# Sheet1.net
KiCad netlist of a schematic drawn in Altium Designer
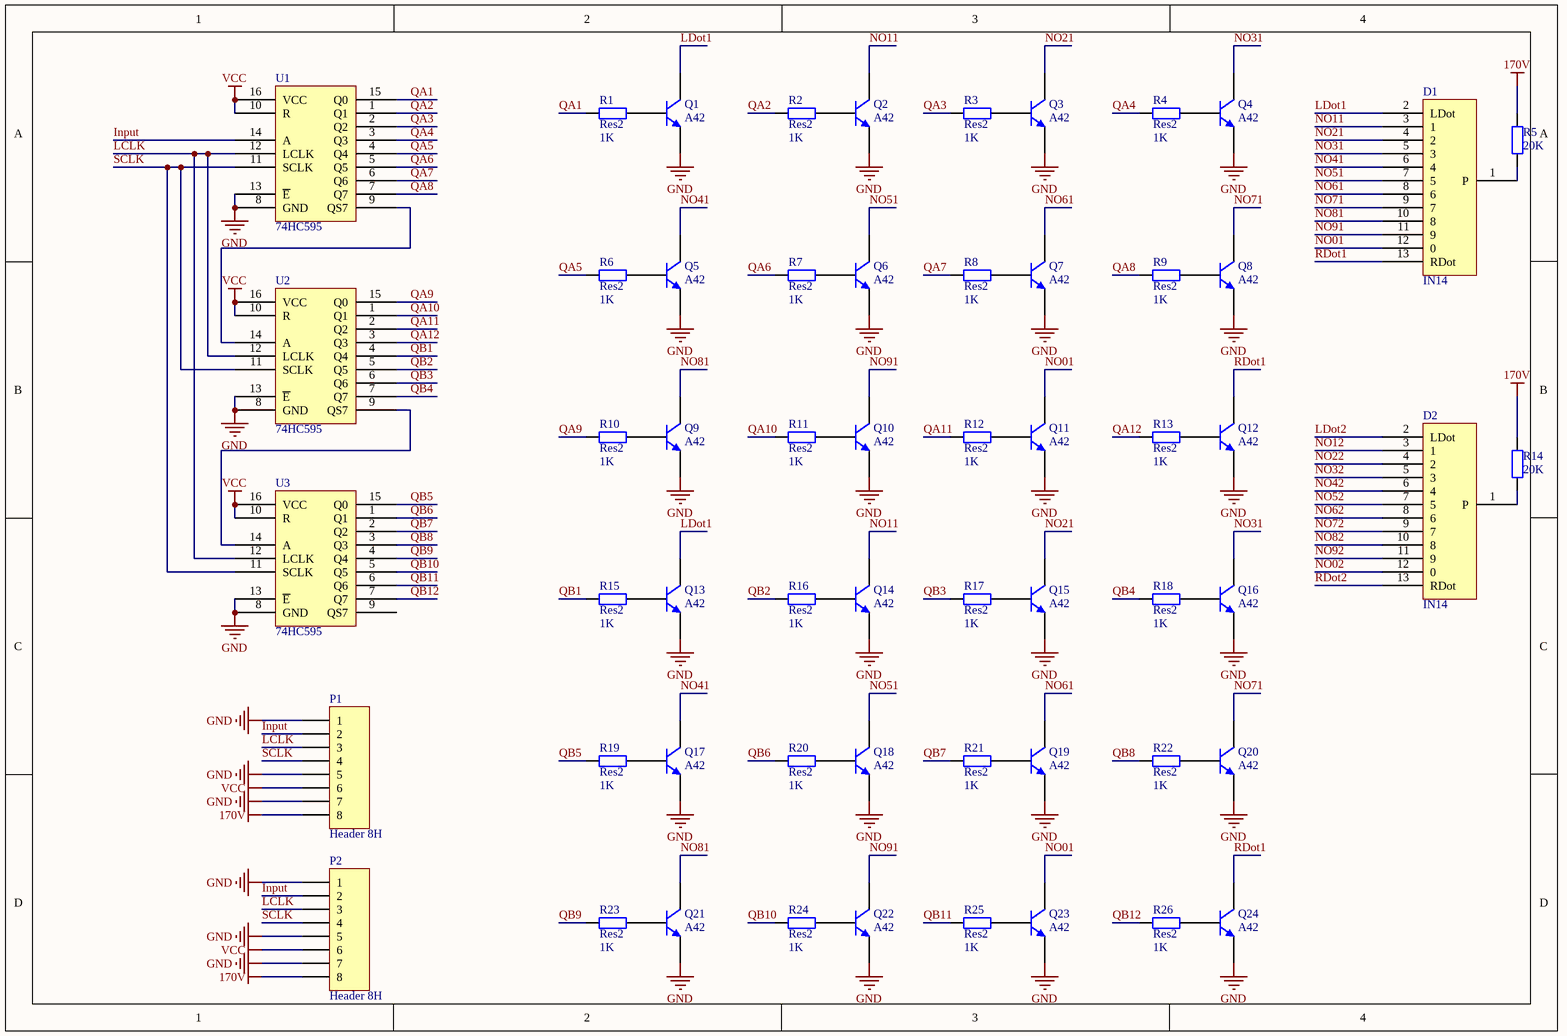
[diagram p0: Sheet1.SchDoc]

(export (version "E")
  (design (tool "Eeschema 10.0.6"))
  (components
    (comp (ref "D1") (value "IN14") (footprint "IN14") (libsource (lib "Schlib1") (part "IN14")))
    (comp (ref "D2") (value "IN14") (footprint "IN14") (libsource (lib "Schlib1") (part "IN14")))
    (comp (ref "P1")
      (value "Header 8H")
      (footprint "HDR1X8H")
      (description "Header, 8-Pin, Right Angle")
      (fields (field (name "PUBLISHER") "Altium Limited"))
      (libsource (lib "Miscellaneous Connectors") (part "Header 8H"))
    )
    (comp (ref "P2")
      (value "Header 8H")
      (footprint "HDR1X8H")
      (description "Header, 8-Pin, Right Angle")
      (fields (field (name "PUBLISHER") "Altium Limited"))
      (libsource (lib "Miscellaneous Connectors") (part "Header 8H"))
    )
    (comp (ref "Q1")
      (value "A42")
      (footprint "SOT-23")
      (description "NPN General Purpose Amplifier")
      (fields (field (name "PUBLISHER") "Altium Limited"))
      (libsource (lib "Miscellaneous Devices") (part "2N3904"))
    )
    (comp (ref "Q2")
      (value "A42")
      (footprint "SOT-23")
      (description "NPN General Purpose Amplifier")
      (fields (field (name "PUBLISHER") "Altium Limited"))
      (libsource (lib "Miscellaneous Devices") (part "2N3904"))
    )
    (comp (ref "Q3")
      (value "A42")
      (footprint "SOT-23")
      (description "NPN General Purpose Amplifier")
      (fields (field (name "PUBLISHER") "Altium Limited"))
      (libsource (lib "Miscellaneous Devices") (part "2N3904"))
    )
    (comp (ref "Q4")
      (value "A42")
      (footprint "SOT-23")
      (description "NPN General Purpose Amplifier")
      (fields (field (name "PUBLISHER") "Altium Limited"))
      (libsource (lib "Miscellaneous Devices") (part "2N3904"))
    )
    (comp (ref "Q5")
      (value "A42")
      (footprint "SOT-23")
      (description "NPN General Purpose Amplifier")
      (fields (field (name "PUBLISHER") "Altium Limited"))
      (libsource (lib "Miscellaneous Devices") (part "2N3904"))
    )
    (comp (ref "Q6")
      (value "A42")
      (footprint "SOT-23")
      (description "NPN General Purpose Amplifier")
      (fields (field (name "PUBLISHER") "Altium Limited"))
      (libsource (lib "Miscellaneous Devices") (part "2N3904"))
    )
    (comp (ref "Q7")
      (value "A42")
      (footprint "SOT-23")
      (description "NPN General Purpose Amplifier")
      (fields (field (name "PUBLISHER") "Altium Limited"))
      (libsource (lib "Miscellaneous Devices") (part "2N3904"))
    )
    (comp (ref "Q8")
      (value "A42")
      (footprint "SOT-23")
      (description "NPN General Purpose Amplifier")
      (fields (field (name "PUBLISHER") "Altium Limited"))
      (libsource (lib "Miscellaneous Devices") (part "2N3904"))
    )
    (comp (ref "Q9")
      (value "A42")
      (footprint "SOT-23")
      (description "NPN General Purpose Amplifier")
      (fields (field (name "PUBLISHER") "Altium Limited"))
      (libsource (lib "Miscellaneous Devices") (part "2N3904"))
    )
    (comp (ref "Q10")
      (value "A42")
      (footprint "SOT-23")
      (description "NPN General Purpose Amplifier")
      (fields (field (name "PUBLISHER") "Altium Limited"))
      (libsource (lib "Miscellaneous Devices") (part "2N3904"))
    )
    (comp (ref "Q11")
      (value "A42")
      (footprint "SOT-23")
      (description "NPN General Purpose Amplifier")
      (fields (field (name "PUBLISHER") "Altium Limited"))
      (libsource (lib "Miscellaneous Devices") (part "2N3904"))
    )
    (comp (ref "Q12")
      (value "A42")
      (footprint "SOT-23")
      (description "NPN General Purpose Amplifier")
      (fields (field (name "PUBLISHER") "Altium Limited"))
      (libsource (lib "Miscellaneous Devices") (part "2N3904"))
    )
    (comp (ref "Q13")
      (value "A42")
      (footprint "SOT-23")
      (description "NPN General Purpose Amplifier")
      (fields (field (name "PUBLISHER") "Altium Limited"))
      (libsource (lib "Miscellaneous Devices") (part "2N3904"))
    )
    (comp (ref "Q14")
      (value "A42")
      (footprint "SOT-23")
      (description "NPN General Purpose Amplifier")
      (fields (field (name "PUBLISHER") "Altium Limited"))
      (libsource (lib "Miscellaneous Devices") (part "2N3904"))
    )
    (comp (ref "Q15")
      (value "A42")
      (footprint "SOT-23")
      (description "NPN General Purpose Amplifier")
      (fields (field (name "PUBLISHER") "Altium Limited"))
      (libsource (lib "Miscellaneous Devices") (part "2N3904"))
    )
    (comp (ref "Q16")
      (value "A42")
      (footprint "SOT-23")
      (description "NPN General Purpose Amplifier")
      (fields (field (name "PUBLISHER") "Altium Limited"))
      (libsource (lib "Miscellaneous Devices") (part "2N3904"))
    )
    (comp (ref "Q17")
      (value "A42")
      (footprint "SOT-23")
      (description "NPN General Purpose Amplifier")
      (fields (field (name "PUBLISHER") "Altium Limited"))
      (libsource (lib "Miscellaneous Devices") (part "2N3904"))
    )
    (comp (ref "Q18")
      (value "A42")
      (footprint "SOT-23")
      (description "NPN General Purpose Amplifier")
      (fields (field (name "PUBLISHER") "Altium Limited"))
      (libsource (lib "Miscellaneous Devices") (part "2N3904"))
    )
    (comp (ref "Q19")
      (value "A42")
      (footprint "SOT-23")
      (description "NPN General Purpose Amplifier")
      (fields (field (name "PUBLISHER") "Altium Limited"))
      (libsource (lib "Miscellaneous Devices") (part "2N3904"))
    )
    (comp (ref "Q20")
      (value "A42")
      (footprint "SOT-23")
      (description "NPN General Purpose Amplifier")
      (fields (field (name "PUBLISHER") "Altium Limited"))
      (libsource (lib "Miscellaneous Devices") (part "2N3904"))
    )
    (comp (ref "Q21")
      (value "A42")
      (footprint "SOT-23")
      (description "NPN General Purpose Amplifier")
      (fields (field (name "PUBLISHER") "Altium Limited"))
      (libsource (lib "Miscellaneous Devices") (part "2N3904"))
    )
    (comp (ref "Q22")
      (value "A42")
      (footprint "SOT-23")
      (description "NPN General Purpose Amplifier")
      (fields (field (name "PUBLISHER") "Altium Limited"))
      (libsource (lib "Miscellaneous Devices") (part "2N3904"))
    )
    (comp (ref "Q23")
      (value "A42")
      (footprint "SOT-23")
      (description "NPN General Purpose Amplifier")
      (fields (field (name "PUBLISHER") "Altium Limited"))
      (libsource (lib "Miscellaneous Devices") (part "2N3904"))
    )
    (comp (ref "Q24")
      (value "A42")
      (footprint "SOT-23")
      (description "NPN General Purpose Amplifier")
      (fields (field (name "PUBLISHER") "Altium Limited"))
      (libsource (lib "Miscellaneous Devices") (part "2N3904"))
    )
    (comp (ref "R1")
      (value "Res2")
      (footprint "0805-0R")
      (description "Resistor")
      (fields (field (name "ALTIUM_VALUE") "1K") (field (name "PUBLISHER") "Altium Limited"))
      (libsource (lib "Miscellaneous Devices") (part "Res2"))
    )
    (comp (ref "R2")
      (value "Res2")
      (footprint "AXIAL-0.4")
      (description "Resistor")
      (fields (field (name "ALTIUM_VALUE") "1K") (field (name "PUBLISHER") "Altium Limited"))
      (libsource (lib "Miscellaneous Devices") (part "Res2"))
    )
    (comp (ref "R3")
      (value "Res2")
      (footprint "AXIAL-0.4")
      (description "Resistor")
      (fields (field (name "ALTIUM_VALUE") "1K") (field (name "PUBLISHER") "Altium Limited"))
      (libsource (lib "Miscellaneous Devices") (part "Res2"))
    )
    (comp (ref "R4")
      (value "Res2")
      (footprint "AXIAL-0.4")
      (description "Resistor")
      (fields (field (name "ALTIUM_VALUE") "1K") (field (name "PUBLISHER") "Altium Limited"))
      (libsource (lib "Miscellaneous Devices") (part "Res2"))
    )
    (comp (ref "R5")
      (value "20K")
      (footprint "0805-0R")
      (description "Resistor")
      (fields (field (name "PUBLISHER") "Altium Limited"))
      (libsource (lib "") (part "Res2_1"))
    )
    (comp (ref "R6")
      (value "Res2")
      (footprint "AXIAL-0.4")
      (description "Resistor")
      (fields (field (name "ALTIUM_VALUE") "1K") (field (name "PUBLISHER") "Altium Limited"))
      (libsource (lib "Miscellaneous Devices") (part "Res2"))
    )
    (comp (ref "R7")
      (value "Res2")
      (footprint "AXIAL-0.4")
      (description "Resistor")
      (fields (field (name "ALTIUM_VALUE") "1K") (field (name "PUBLISHER") "Altium Limited"))
      (libsource (lib "Miscellaneous Devices") (part "Res2"))
    )
    (comp (ref "R8")
      (value "Res2")
      (footprint "AXIAL-0.4")
      (description "Resistor")
      (fields (field (name "ALTIUM_VALUE") "1K") (field (name "PUBLISHER") "Altium Limited"))
      (libsource (lib "Miscellaneous Devices") (part "Res2"))
    )
    (comp (ref "R9")
      (value "Res2")
      (footprint "AXIAL-0.4")
      (description "Resistor")
      (fields (field (name "ALTIUM_VALUE") "1K") (field (name "PUBLISHER") "Altium Limited"))
      (libsource (lib "Miscellaneous Devices") (part "Res2"))
    )
    (comp (ref "R10")
      (value "Res2")
      (footprint "AXIAL-0.4")
      (description "Resistor")
      (fields (field (name "ALTIUM_VALUE") "1K") (field (name "PUBLISHER") "Altium Limited"))
      (libsource (lib "Miscellaneous Devices") (part "Res2"))
    )
    (comp (ref "R11")
      (value "Res2")
      (footprint "AXIAL-0.4")
      (description "Resistor")
      (fields (field (name "ALTIUM_VALUE") "1K") (field (name "PUBLISHER") "Altium Limited"))
      (libsource (lib "Miscellaneous Devices") (part "Res2"))
    )
    (comp (ref "R12")
      (value "Res2")
      (footprint "AXIAL-0.4")
      (description "Resistor")
      (fields (field (name "ALTIUM_VALUE") "1K") (field (name "PUBLISHER") "Altium Limited"))
      (libsource (lib "Miscellaneous Devices") (part "Res2"))
    )
    (comp (ref "R13")
      (value "Res2")
      (footprint "AXIAL-0.4")
      (description "Resistor")
      (fields (field (name "ALTIUM_VALUE") "1K") (field (name "PUBLISHER") "Altium Limited"))
      (libsource (lib "Miscellaneous Devices") (part "Res2"))
    )
    (comp (ref "R14")
      (value "20K")
      (footprint "0805-0R")
      (description "Resistor")
      (fields (field (name "PUBLISHER") "Altium Limited"))
      (libsource (lib "") (part "Res2_1"))
    )
    (comp (ref "R15")
      (value "Res2")
      (footprint "AXIAL-0.4")
      (description "Resistor")
      (fields (field (name "ALTIUM_VALUE") "1K") (field (name "PUBLISHER") "Altium Limited"))
      (libsource (lib "Miscellaneous Devices") (part "Res2"))
    )
    (comp (ref "R16")
      (value "Res2")
      (footprint "AXIAL-0.4")
      (description "Resistor")
      (fields (field (name "ALTIUM_VALUE") "1K") (field (name "PUBLISHER") "Altium Limited"))
      (libsource (lib "Miscellaneous Devices") (part "Res2"))
    )
    (comp (ref "R17")
      (value "Res2")
      (footprint "AXIAL-0.4")
      (description "Resistor")
      (fields (field (name "ALTIUM_VALUE") "1K") (field (name "PUBLISHER") "Altium Limited"))
      (libsource (lib "Miscellaneous Devices") (part "Res2"))
    )
    (comp (ref "R18")
      (value "Res2")
      (footprint "AXIAL-0.4")
      (description "Resistor")
      (fields (field (name "ALTIUM_VALUE") "1K") (field (name "PUBLISHER") "Altium Limited"))
      (libsource (lib "Miscellaneous Devices") (part "Res2"))
    )
    (comp (ref "R19")
      (value "Res2")
      (footprint "AXIAL-0.4")
      (description "Resistor")
      (fields (field (name "ALTIUM_VALUE") "1K") (field (name "PUBLISHER") "Altium Limited"))
      (libsource (lib "Miscellaneous Devices") (part "Res2"))
    )
    (comp (ref "R20")
      (value "Res2")
      (footprint "AXIAL-0.4")
      (description "Resistor")
      (fields (field (name "ALTIUM_VALUE") "1K") (field (name "PUBLISHER") "Altium Limited"))
      (libsource (lib "Miscellaneous Devices") (part "Res2"))
    )
    (comp (ref "R21")
      (value "Res2")
      (footprint "AXIAL-0.4")
      (description "Resistor")
      (fields (field (name "ALTIUM_VALUE") "1K") (field (name "PUBLISHER") "Altium Limited"))
      (libsource (lib "Miscellaneous Devices") (part "Res2"))
    )
    (comp (ref "R22")
      (value "Res2")
      (footprint "AXIAL-0.4")
      (description "Resistor")
      (fields (field (name "ALTIUM_VALUE") "1K") (field (name "PUBLISHER") "Altium Limited"))
      (libsource (lib "Miscellaneous Devices") (part "Res2"))
    )
    (comp (ref "R23")
      (value "Res2")
      (footprint "AXIAL-0.4")
      (description "Resistor")
      (fields (field (name "ALTIUM_VALUE") "1K") (field (name "PUBLISHER") "Altium Limited"))
      (libsource (lib "Miscellaneous Devices") (part "Res2"))
    )
    (comp (ref "R24")
      (value "Res2")
      (footprint "AXIAL-0.4")
      (description "Resistor")
      (fields (field (name "ALTIUM_VALUE") "1K") (field (name "PUBLISHER") "Altium Limited"))
      (libsource (lib "Miscellaneous Devices") (part "Res2"))
    )
    (comp (ref "R25")
      (value "Res2")
      (footprint "AXIAL-0.4")
      (description "Resistor")
      (fields (field (name "ALTIUM_VALUE") "1K") (field (name "PUBLISHER") "Altium Limited"))
      (libsource (lib "Miscellaneous Devices") (part "Res2"))
    )
    (comp (ref "R26")
      (value "Res2")
      (footprint "AXIAL-0.4")
      (description "Resistor")
      (fields (field (name "ALTIUM_VALUE") "1K") (field (name "PUBLISHER") "Altium Limited"))
      (libsource (lib "Miscellaneous Devices") (part "Res2"))
    )
    (comp (ref "U1") (value "74HC595") (footprint "SOP16") (libsource (lib "74HC595") (part "74HC595")))
    (comp (ref "U2") (value "74HC595") (footprint "SOP16") (libsource (lib "74HC595") (part "74HC595")))
    (comp (ref "U3") (value "74HC595") (footprint "SOP16") (libsource (lib "74HC595") (part "74HC595")))
  )
  (nets
    (net (code "1") (name "/Input") (class "Default")
      (node (ref "P1") (pin "2") (pinfunction "2_2") (pintype "passive"))
      (node (ref "P2") (pin "2") (pinfunction "2_2") (pintype "passive"))
      (node (ref "U1") (pin "14") (pinfunction "A_14") (pintype "passive"))
    )
    (net (code "2") (name "/LCLK") (class "Default")
      (node (ref "P1") (pin "3") (pinfunction "3_3") (pintype "passive"))
      (node (ref "P2") (pin "3") (pinfunction "3_3") (pintype "passive"))
      (node (ref "U1") (pin "12") (pinfunction "LCLK_12") (pintype "passive"))
      (node (ref "U2") (pin "12") (pinfunction "LCLK_12") (pintype "passive"))
      (node (ref "U3") (pin "12") (pinfunction "LCLK_12") (pintype "passive"))
    )
    (net (code "3") (name "/LDot1") (class "Default")
      (node (ref "D1") (pin "2") (pinfunction "LDot_2") (pintype "passive"))
      (node (ref "Q1") (pin "3") (pinfunction "C_3") (pintype "passive"))
      (node (ref "Q13") (pin "3") (pinfunction "C_3") (pintype "passive"))
    )
    (net (code "4") (name "/LDot2") (class "Default")
      (node (ref "D2") (pin "2") (pinfunction "LDot_2") (pintype "passive"))
    )
    (net (code "5") (name "/NO01") (class "Default")
      (node (ref "D1") (pin "12") (pinfunction "0_12") (pintype "passive"))
      (node (ref "Q11") (pin "3") (pinfunction "C_3") (pintype "passive"))
      (node (ref "Q23") (pin "3") (pinfunction "C_3") (pintype "passive"))
    )
    (net (code "6") (name "/NO02") (class "Default")
      (node (ref "D2") (pin "12") (pinfunction "0_12") (pintype "passive"))
    )
    (net (code "7") (name "/NO11") (class "Default")
      (node (ref "D1") (pin "3") (pinfunction "1_3") (pintype "passive"))
      (node (ref "Q14") (pin "3") (pinfunction "C_3") (pintype "passive"))
      (node (ref "Q2") (pin "3") (pinfunction "C_3") (pintype "passive"))
    )
    (net (code "8") (name "/NO12") (class "Default")
      (node (ref "D2") (pin "3") (pinfunction "1_3") (pintype "passive"))
    )
    (net (code "9") (name "/NO21") (class "Default")
      (node (ref "D1") (pin "4") (pinfunction "2_4") (pintype "passive"))
      (node (ref "Q15") (pin "3") (pinfunction "C_3") (pintype "passive"))
      (node (ref "Q3") (pin "3") (pinfunction "C_3") (pintype "passive"))
    )
    (net (code "10") (name "/NO22") (class "Default")
      (node (ref "D2") (pin "4") (pinfunction "2_4") (pintype "passive"))
    )
    (net (code "11") (name "/NO31") (class "Default")
      (node (ref "D1") (pin "5") (pinfunction "3_5") (pintype "passive"))
      (node (ref "Q16") (pin "3") (pinfunction "C_3") (pintype "passive"))
      (node (ref "Q4") (pin "3") (pinfunction "C_3") (pintype "passive"))
    )
    (net (code "12") (name "/NO32") (class "Default")
      (node (ref "D2") (pin "5") (pinfunction "3_5") (pintype "passive"))
    )
    (net (code "13") (name "/NO41") (class "Default")
      (node (ref "D1") (pin "6") (pinfunction "4_6") (pintype "passive"))
      (node (ref "Q17") (pin "3") (pinfunction "C_3") (pintype "passive"))
      (node (ref "Q5") (pin "3") (pinfunction "C_3") (pintype "passive"))
    )
    (net (code "14") (name "/NO42") (class "Default")
      (node (ref "D2") (pin "6") (pinfunction "4_6") (pintype "passive"))
    )
    (net (code "15") (name "/NO51") (class "Default")
      (node (ref "D1") (pin "7") (pinfunction "5_7") (pintype "passive"))
      (node (ref "Q18") (pin "3") (pinfunction "C_3") (pintype "passive"))
      (node (ref "Q6") (pin "3") (pinfunction "C_3") (pintype "passive"))
    )
    (net (code "16") (name "/NO52") (class "Default")
      (node (ref "D2") (pin "7") (pinfunction "5_7") (pintype "passive"))
    )
    (net (code "17") (name "/NO61") (class "Default")
      (node (ref "D1") (pin "8") (pinfunction "6_8") (pintype "passive"))
      (node (ref "Q19") (pin "3") (pinfunction "C_3") (pintype "passive"))
      (node (ref "Q7") (pin "3") (pinfunction "C_3") (pintype "passive"))
    )
    (net (code "18") (name "/NO62") (class "Default")
      (node (ref "D2") (pin "8") (pinfunction "6_8") (pintype "passive"))
    )
    (net (code "19") (name "/NO71") (class "Default")
      (node (ref "D1") (pin "9") (pinfunction "7_9") (pintype "passive"))
      (node (ref "Q20") (pin "3") (pinfunction "C_3") (pintype "passive"))
      (node (ref "Q8") (pin "3") (pinfunction "C_3") (pintype "passive"))
    )
    (net (code "20") (name "/NO72") (class "Default")
      (node (ref "D2") (pin "9") (pinfunction "7_9") (pintype "passive"))
    )
    (net (code "21") (name "/NO81") (class "Default")
      (node (ref "D1") (pin "10") (pinfunction "8_10") (pintype "passive"))
      (node (ref "Q21") (pin "3") (pinfunction "C_3") (pintype "passive"))
      (node (ref "Q9") (pin "3") (pinfunction "C_3") (pintype "passive"))
    )
    (net (code "22") (name "/NO82") (class "Default")
      (node (ref "D2") (pin "10") (pinfunction "8_10") (pintype "passive"))
    )
    (net (code "23") (name "/NO91") (class "Default")
      (node (ref "D1") (pin "11") (pinfunction "9_11") (pintype "passive"))
      (node (ref "Q10") (pin "3") (pinfunction "C_3") (pintype "passive"))
      (node (ref "Q22") (pin "3") (pinfunction "C_3") (pintype "passive"))
    )
    (net (code "24") (name "/NO92") (class "Default")
      (node (ref "D2") (pin "11") (pinfunction "9_11") (pintype "passive"))
    )
    (net (code "25") (name "/QA1") (class "Default")
      (node (ref "R1") (pin "1") (pinfunction "1_1") (pintype "passive"))
      (node (ref "U1") (pin "15") (pinfunction "Q0_15") (pintype "passive"))
    )
    (net (code "26") (name "/QA2") (class "Default")
      (node (ref "R2") (pin "1") (pinfunction "1_1") (pintype "passive"))
      (node (ref "U1") (pin "1") (pinfunction "Q1_1") (pintype "passive"))
    )
    (net (code "27") (name "/QA3") (class "Default")
      (node (ref "R3") (pin "1") (pinfunction "1_1") (pintype "passive"))
      (node (ref "U1") (pin "2") (pinfunction "Q2_2") (pintype "passive"))
    )
    (net (code "28") (name "/QA4") (class "Default")
      (node (ref "R4") (pin "1") (pinfunction "1_1") (pintype "passive"))
      (node (ref "U1") (pin "3") (pinfunction "Q3_3") (pintype "passive"))
    )
    (net (code "29") (name "/QA5") (class "Default")
      (node (ref "R6") (pin "1") (pinfunction "1_1") (pintype "passive"))
      (node (ref "U1") (pin "4") (pinfunction "Q4_4") (pintype "passive"))
    )
    (net (code "30") (name "/QA6") (class "Default")
      (node (ref "R7") (pin "1") (pinfunction "1_1") (pintype "passive"))
      (node (ref "U1") (pin "5") (pinfunction "Q5_5") (pintype "passive"))
    )
    (net (code "31") (name "/QA7") (class "Default")
      (node (ref "R8") (pin "1") (pinfunction "1_1") (pintype "passive"))
      (node (ref "U1") (pin "6") (pinfunction "Q6_6") (pintype "passive"))
    )
    (net (code "32") (name "/QA8") (class "Default")
      (node (ref "R9") (pin "1") (pinfunction "1_1") (pintype "passive"))
      (node (ref "U1") (pin "7") (pinfunction "Q7_7") (pintype "passive"))
    )
    (net (code "33") (name "/QA9") (class "Default")
      (node (ref "R10") (pin "1") (pinfunction "1_1") (pintype "passive"))
      (node (ref "U2") (pin "15") (pinfunction "Q0_15") (pintype "passive"))
    )
    (net (code "34") (name "/QA10") (class "Default")
      (node (ref "R11") (pin "1") (pinfunction "1_1") (pintype "passive"))
      (node (ref "U2") (pin "1") (pinfunction "Q1_1") (pintype "passive"))
    )
    (net (code "35") (name "/QA11") (class "Default")
      (node (ref "R12") (pin "1") (pinfunction "1_1") (pintype "passive"))
      (node (ref "U2") (pin "2") (pinfunction "Q2_2") (pintype "passive"))
    )
    (net (code "36") (name "/QA12") (class "Default")
      (node (ref "R13") (pin "1") (pinfunction "1_1") (pintype "passive"))
      (node (ref "U2") (pin "3") (pinfunction "Q3_3") (pintype "passive"))
    )
    (net (code "37") (name "/QB1") (class "Default")
      (node (ref "R15") (pin "1") (pinfunction "1_1") (pintype "passive"))
      (node (ref "U2") (pin "4") (pinfunction "Q4_4") (pintype "passive"))
    )
    (net (code "38") (name "/QB2") (class "Default")
      (node (ref "R16") (pin "1") (pinfunction "1_1") (pintype "passive"))
      (node (ref "U2") (pin "5") (pinfunction "Q5_5") (pintype "passive"))
    )
    (net (code "39") (name "/QB3") (class "Default")
      (node (ref "R17") (pin "1") (pinfunction "1_1") (pintype "passive"))
      (node (ref "U2") (pin "6") (pinfunction "Q6_6") (pintype "passive"))
    )
    (net (code "40") (name "/QB4") (class "Default")
      (node (ref "R18") (pin "1") (pinfunction "1_1") (pintype "passive"))
      (node (ref "U2") (pin "7") (pinfunction "Q7_7") (pintype "passive"))
    )
    (net (code "41") (name "/QB5") (class "Default")
      (node (ref "R19") (pin "1") (pinfunction "1_1") (pintype "passive"))
      (node (ref "U3") (pin "15") (pinfunction "Q0_15") (pintype "passive"))
    )
    (net (code "42") (name "/QB6") (class "Default")
      (node (ref "R20") (pin "1") (pinfunction "1_1") (pintype "passive"))
      (node (ref "U3") (pin "1") (pinfunction "Q1_1") (pintype "passive"))
    )
    (net (code "43") (name "/QB7") (class "Default")
      (node (ref "R21") (pin "1") (pinfunction "1_1") (pintype "passive"))
      (node (ref "U3") (pin "2") (pinfunction "Q2_2") (pintype "passive"))
    )
    (net (code "44") (name "/QB8") (class "Default")
      (node (ref "R22") (pin "1") (pinfunction "1_1") (pintype "passive"))
      (node (ref "U3") (pin "3") (pinfunction "Q3_3") (pintype "passive"))
    )
    (net (code "45") (name "/QB9") (class "Default")
      (node (ref "R23") (pin "1") (pinfunction "1_1") (pintype "passive"))
      (node (ref "U3") (pin "4") (pinfunction "Q4_4") (pintype "passive"))
    )
    (net (code "46") (name "/QB10") (class "Default")
      (node (ref "R24") (pin "1") (pinfunction "1_1") (pintype "passive"))
      (node (ref "U3") (pin "5") (pinfunction "Q5_5") (pintype "passive"))
    )
    (net (code "47") (name "/QB11") (class "Default")
      (node (ref "R25") (pin "1") (pinfunction "1_1") (pintype "passive"))
      (node (ref "U3") (pin "6") (pinfunction "Q6_6") (pintype "passive"))
    )
    (net (code "48") (name "/QB12") (class "Default")
      (node (ref "R26") (pin "1") (pinfunction "1_1") (pintype "passive"))
      (node (ref "U3") (pin "7") (pinfunction "Q7_7") (pintype "passive"))
    )
    (net (code "49") (name "/RDot1") (class "Default")
      (node (ref "D1") (pin "13") (pinfunction "RDot_13") (pintype "passive"))
      (node (ref "Q12") (pin "3") (pinfunction "C_3") (pintype "passive"))
      (node (ref "Q24") (pin "3") (pinfunction "C_3") (pintype "passive"))
    )
    (net (code "50") (name "/RDot2") (class "Default")
      (node (ref "D2") (pin "13") (pinfunction "RDot_13") (pintype "passive"))
    )
    (net (code "51") (name "/SCLK") (class "Default")
      (node (ref "P1") (pin "4") (pinfunction "4_4") (pintype "passive"))
      (node (ref "P2") (pin "4") (pinfunction "4_4") (pintype "passive"))
      (node (ref "U1") (pin "11") (pinfunction "SCLK_11") (pintype "passive"))
      (node (ref "U2") (pin "11") (pinfunction "SCLK_11") (pintype "passive"))
      (node (ref "U3") (pin "11") (pinfunction "SCLK_11") (pintype "passive"))
    )
    (net (code "52") (name "170V") (class "Default")
      (node (ref "P1") (pin "8") (pinfunction "8_8") (pintype "passive"))
      (node (ref "P2") (pin "8") (pinfunction "8_8") (pintype "passive"))
      (node (ref "R14") (pin "2") (pinfunction "2_2") (pintype "passive"))
      (node (ref "R5") (pin "2") (pinfunction "2_2") (pintype "passive"))
    )
    (net (code "53") (name "GND") (class "Default")
      (node (ref "P1") (pin "1") (pinfunction "1_1") (pintype "passive"))
      (node (ref "P1") (pin "5") (pinfunction "5_5") (pintype "passive"))
      (node (ref "P1") (pin "7") (pinfunction "7_7") (pintype "passive"))
      (node (ref "P2") (pin "1") (pinfunction "1_1") (pintype "passive"))
      (node (ref "P2") (pin "5") (pinfunction "5_5") (pintype "passive"))
      (node (ref "P2") (pin "7") (pinfunction "7_7") (pintype "passive"))
      (node (ref "Q1") (pin "1") (pinfunction "E_1") (pintype "passive"))
      (node (ref "Q10") (pin "1") (pinfunction "E_1") (pintype "passive"))
      (node (ref "Q11") (pin "1") (pinfunction "E_1") (pintype "passive"))
      (node (ref "Q12") (pin "1") (pinfunction "E_1") (pintype "passive"))
      (node (ref "Q13") (pin "1") (pinfunction "E_1") (pintype "passive"))
      (node (ref "Q14") (pin "1") (pinfunction "E_1") (pintype "passive"))
      (node (ref "Q15") (pin "1") (pinfunction "E_1") (pintype "passive"))
      (node (ref "Q16") (pin "1") (pinfunction "E_1") (pintype "passive"))
      (node (ref "Q17") (pin "1") (pinfunction "E_1") (pintype "passive"))
      (node (ref "Q18") (pin "1") (pinfunction "E_1") (pintype "passive"))
      (node (ref "Q19") (pin "1") (pinfunction "E_1") (pintype "passive"))
      (node (ref "Q2") (pin "1") (pinfunction "E_1") (pintype "passive"))
      (node (ref "Q20") (pin "1") (pinfunction "E_1") (pintype "passive"))
      (node (ref "Q21") (pin "1") (pinfunction "E_1") (pintype "passive"))
      (node (ref "Q22") (pin "1") (pinfunction "E_1") (pintype "passive"))
      (node (ref "Q23") (pin "1") (pinfunction "E_1") (pintype "passive"))
      (node (ref "Q24") (pin "1") (pinfunction "E_1") (pintype "passive"))
      (node (ref "Q3") (pin "1") (pinfunction "E_1") (pintype "passive"))
      (node (ref "Q4") (pin "1") (pinfunction "E_1") (pintype "passive"))
      (node (ref "Q5") (pin "1") (pinfunction "E_1") (pintype "passive"))
      (node (ref "Q6") (pin "1") (pinfunction "E_1") (pintype "passive"))
      (node (ref "Q7") (pin "1") (pinfunction "E_1") (pintype "passive"))
      (node (ref "Q8") (pin "1") (pinfunction "E_1") (pintype "passive"))
      (node (ref "Q9") (pin "1") (pinfunction "E_1") (pintype "passive"))
      (node (ref "U1") (pin "13") (pinfunction "~{E}_13") (pintype "passive"))
      (node (ref "U1") (pin "8") (pinfunction "GND_8") (pintype "passive"))
      (node (ref "U2") (pin "13") (pinfunction "~{E}_13") (pintype "passive"))
      (node (ref "U2") (pin "8") (pinfunction "GND_8") (pintype "passive"))
      (node (ref "U3") (pin "13") (pinfunction "~{E}_13") (pintype "passive"))
      (node (ref "U3") (pin "8") (pinfunction "GND_8") (pintype "passive"))
    )
    (net (code "54") (name "Net-(D1-P)") (class "Default")
      (node (ref "D1") (pin "1") (pinfunction "P_1") (pintype "passive"))
      (node (ref "R5") (pin "1") (pinfunction "1_1") (pintype "passive"))
    )
    (net (code "55") (name "Net-(D2-P)") (class "Default")
      (node (ref "D2") (pin "1") (pinfunction "P_1") (pintype "passive"))
      (node (ref "R14") (pin "1") (pinfunction "1_1") (pintype "passive"))
    )
    (net (code "56") (name "Net-(Q1-B)") (class "Default")
      (node (ref "Q1") (pin "2") (pinfunction "B_2") (pintype "passive"))
      (node (ref "R1") (pin "2") (pinfunction "2_2") (pintype "passive"))
    )
    (net (code "57") (name "Net-(Q2-B)") (class "Default")
      (node (ref "Q2") (pin "2") (pinfunction "B_2") (pintype "passive"))
      (node (ref "R2") (pin "2") (pinfunction "2_2") (pintype "passive"))
    )
    (net (code "58") (name "Net-(Q3-B)") (class "Default")
      (node (ref "Q3") (pin "2") (pinfunction "B_2") (pintype "passive"))
      (node (ref "R3") (pin "2") (pinfunction "2_2") (pintype "passive"))
    )
    (net (code "59") (name "Net-(Q4-B)") (class "Default")
      (node (ref "Q4") (pin "2") (pinfunction "B_2") (pintype "passive"))
      (node (ref "R4") (pin "2") (pinfunction "2_2") (pintype "passive"))
    )
    (net (code "60") (name "Net-(Q5-B)") (class "Default")
      (node (ref "Q5") (pin "2") (pinfunction "B_2") (pintype "passive"))
      (node (ref "R6") (pin "2") (pinfunction "2_2") (pintype "passive"))
    )
    (net (code "61") (name "Net-(Q6-B)") (class "Default")
      (node (ref "Q6") (pin "2") (pinfunction "B_2") (pintype "passive"))
      (node (ref "R7") (pin "2") (pinfunction "2_2") (pintype "passive"))
    )
    (net (code "62") (name "Net-(Q7-B)") (class "Default")
      (node (ref "Q7") (pin "2") (pinfunction "B_2") (pintype "passive"))
      (node (ref "R8") (pin "2") (pinfunction "2_2") (pintype "passive"))
    )
    (net (code "63") (name "Net-(Q8-B)") (class "Default")
      (node (ref "Q8") (pin "2") (pinfunction "B_2") (pintype "passive"))
      (node (ref "R9") (pin "2") (pinfunction "2_2") (pintype "passive"))
    )
    (net (code "64") (name "Net-(Q9-B)") (class "Default")
      (node (ref "Q9") (pin "2") (pinfunction "B_2") (pintype "passive"))
      (node (ref "R10") (pin "2") (pinfunction "2_2") (pintype "passive"))
    )
    (net (code "65") (name "Net-(Q10-B)") (class "Default")
      (node (ref "Q10") (pin "2") (pinfunction "B_2") (pintype "passive"))
      (node (ref "R11") (pin "2") (pinfunction "2_2") (pintype "passive"))
    )
    (net (code "66") (name "Net-(Q11-B)") (class "Default")
      (node (ref "Q11") (pin "2") (pinfunction "B_2") (pintype "passive"))
      (node (ref "R12") (pin "2") (pinfunction "2_2") (pintype "passive"))
    )
    (net (code "67") (name "Net-(Q12-B)") (class "Default")
      (node (ref "Q12") (pin "2") (pinfunction "B_2") (pintype "passive"))
      (node (ref "R13") (pin "2") (pinfunction "2_2") (pintype "passive"))
    )
    (net (code "68") (name "Net-(Q13-B)") (class "Default")
      (node (ref "Q13") (pin "2") (pinfunction "B_2") (pintype "passive"))
      (node (ref "R15") (pin "2") (pinfunction "2_2") (pintype "passive"))
    )
    (net (code "69") (name "Net-(Q14-B)") (class "Default")
      (node (ref "Q14") (pin "2") (pinfunction "B_2") (pintype "passive"))
      (node (ref "R16") (pin "2") (pinfunction "2_2") (pintype "passive"))
    )
    (net (code "70") (name "Net-(Q15-B)") (class "Default")
      (node (ref "Q15") (pin "2") (pinfunction "B_2") (pintype "passive"))
      (node (ref "R17") (pin "2") (pinfunction "2_2") (pintype "passive"))
    )
    (net (code "71") (name "Net-(Q16-B)") (class "Default")
      (node (ref "Q16") (pin "2") (pinfunction "B_2") (pintype "passive"))
      (node (ref "R18") (pin "2") (pinfunction "2_2") (pintype "passive"))
    )
    (net (code "72") (name "Net-(Q17-B)") (class "Default")
      (node (ref "Q17") (pin "2") (pinfunction "B_2") (pintype "passive"))
      (node (ref "R19") (pin "2") (pinfunction "2_2") (pintype "passive"))
    )
    (net (code "73") (name "Net-(Q18-B)") (class "Default")
      (node (ref "Q18") (pin "2") (pinfunction "B_2") (pintype "passive"))
      (node (ref "R20") (pin "2") (pinfunction "2_2") (pintype "passive"))
    )
    (net (code "74") (name "Net-(Q19-B)") (class "Default")
      (node (ref "Q19") (pin "2") (pinfunction "B_2") (pintype "passive"))
      (node (ref "R21") (pin "2") (pinfunction "2_2") (pintype "passive"))
    )
    (net (code "75") (name "Net-(Q20-B)") (class "Default")
      (node (ref "Q20") (pin "2") (pinfunction "B_2") (pintype "passive"))
      (node (ref "R22") (pin "2") (pinfunction "2_2") (pintype "passive"))
    )
    (net (code "76") (name "Net-(Q21-B)") (class "Default")
      (node (ref "Q21") (pin "2") (pinfunction "B_2") (pintype "passive"))
      (node (ref "R23") (pin "2") (pinfunction "2_2") (pintype "passive"))
    )
    (net (code "77") (name "Net-(Q22-B)") (class "Default")
      (node (ref "Q22") (pin "2") (pinfunction "B_2") (pintype "passive"))
      (node (ref "R24") (pin "2") (pinfunction "2_2") (pintype "passive"))
    )
    (net (code "78") (name "Net-(Q23-B)") (class "Default")
      (node (ref "Q23") (pin "2") (pinfunction "B_2") (pintype "passive"))
      (node (ref "R25") (pin "2") (pinfunction "2_2") (pintype "passive"))
    )
    (net (code "79") (name "Net-(Q24-B)") (class "Default")
      (node (ref "Q24") (pin "2") (pinfunction "B_2") (pintype "passive"))
      (node (ref "R26") (pin "2") (pinfunction "2_2") (pintype "passive"))
    )
    (net (code "80") (name "Net-(U1-QS7)") (class "Default")
      (node (ref "U1") (pin "9") (pinfunction "QS7_9") (pintype "passive"))
      (node (ref "U2") (pin "14") (pinfunction "A_14") (pintype "passive"))
    )
    (net (code "81") (name "Net-(U2-QS7)") (class "Default")
      (node (ref "U2") (pin "9") (pinfunction "QS7_9") (pintype "passive"))
      (node (ref "U3") (pin "14") (pinfunction "A_14") (pintype "passive"))
    )
    (net (code "82") (name "VCC") (class "Default")
      (node (ref "P1") (pin "6") (pinfunction "6_6") (pintype "passive"))
      (node (ref "P2") (pin "6") (pinfunction "6_6") (pintype "passive"))
      (node (ref "U1") (pin "10") (pinfunction "R_10") (pintype "passive"))
      (node (ref "U1") (pin "16") (pinfunction "VCC_16") (pintype "passive"))
      (node (ref "U2") (pin "10") (pinfunction "R_10") (pintype "passive"))
      (node (ref "U2") (pin "16") (pinfunction "VCC_16") (pintype "passive"))
      (node (ref "U3") (pin "10") (pinfunction "R_10") (pintype "passive"))
      (node (ref "U3") (pin "16") (pinfunction "VCC_16") (pintype "passive"))
    )
    (net (code "83") (name "unconnected-(U3-QS7-Pad9)") (class "Default")
      (node (ref "U3") (pin "9") (pinfunction "QS7_9") (pintype "passive"))
    )
  )
)
